# 02_MCU.net
KiCad netlist of a schematic drawn in Altium Designer
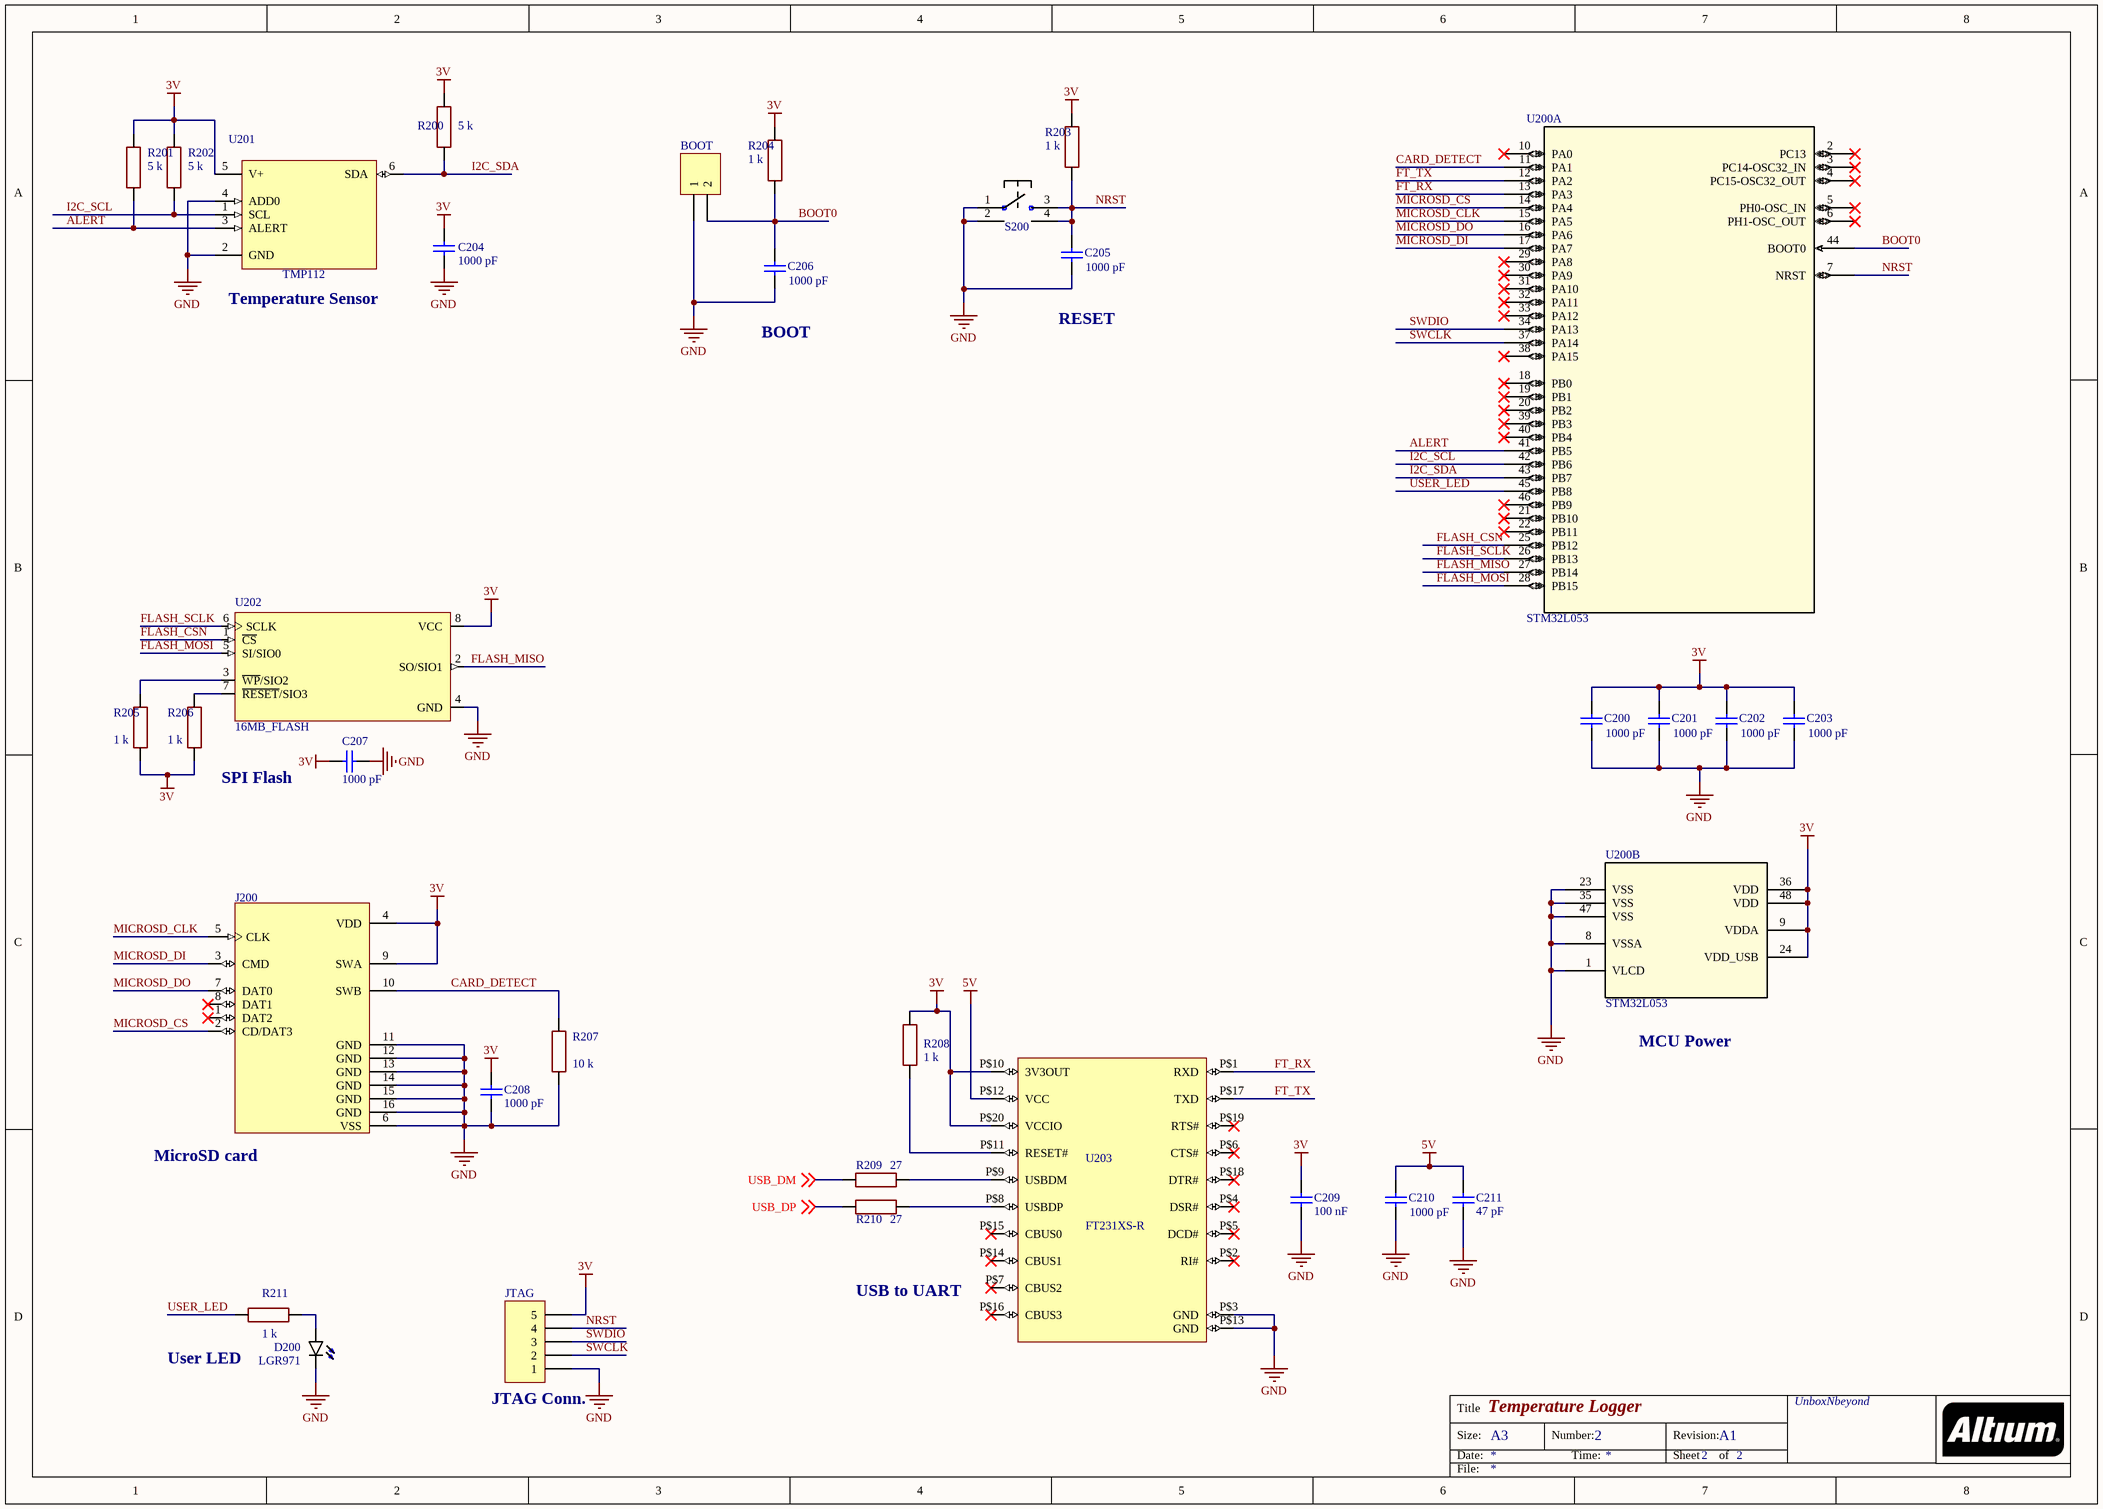
[diagram p0: 02_MCU.SchDoc]

(export (version "E")
  (design (tool "Eeschema 10.0.6"))
  (components
    (comp (ref "BOOT")
      (value "~")
      (footprint "HDR1X2")
      (description "Header, 2-Pin")
      (fields (field (name "PUBLISHER") "Altium Limited"))
      (libsource (lib "Miscellaneous Connectors") (part "Header 2"))
    )
    (comp (ref "C200")
      (value "1000 pF")
      (footprint "C0805")
      (description "CAP CER 1000PF 100V X7R 0805")
      (fields
        (field (name "MANUFACTURER") "KEMET")
        (field (name "MANUFACTURER PART NUMBER") "C0805C102K1RACTU")
      )
      (libsource (lib "temperature_logger_lib") (part "Cap-1000pF"))
    )
    (comp (ref "C201")
      (value "1000 pF")
      (footprint "C0805")
      (description "CAP CER 1000PF 100V X7R 0805")
      (fields
        (field (name "MANUFACTURER") "KEMET")
        (field (name "MANUFACTURER PART NUMBER") "C0805C102K1RACTU")
      )
      (libsource (lib "temperature_logger_lib") (part "Cap-1000pF"))
    )
    (comp (ref "C202")
      (value "1000 pF")
      (footprint "C0805")
      (description "CAP CER 1000PF 100V X7R 0805")
      (fields
        (field (name "MANUFACTURER") "KEMET")
        (field (name "MANUFACTURER PART NUMBER") "C0805C102K1RACTU")
      )
      (libsource (lib "temperature_logger_lib") (part "Cap-1000pF"))
    )
    (comp (ref "C203")
      (value "1000 pF")
      (footprint "C0805")
      (description "CAP CER 1000PF 100V X7R 0805")
      (fields
        (field (name "MANUFACTURER") "KEMET")
        (field (name "MANUFACTURER PART NUMBER") "C0805C102K1RACTU")
      )
      (libsource (lib "temperature_logger_lib") (part "Cap-1000pF"))
    )
    (comp (ref "C204")
      (value "1000 pF")
      (footprint "C0805")
      (description "CAP CER 1000PF 100V X7R 0805")
      (fields
        (field (name "MANUFACTURER") "KEMET")
        (field (name "MANUFACTURER PART NUMBER") "C0805C102K1RACTU")
      )
      (libsource (lib "temperature_logger_lib") (part "Cap-1000pF"))
    )
    (comp (ref "C205")
      (value "1000 pF")
      (footprint "C0805")
      (description "CAP CER 1000PF 100V X7R 0805")
      (fields
        (field (name "MANUFACTURER") "KEMET")
        (field (name "MANUFACTURER PART NUMBER") "C0805C102K1RACTU")
      )
      (libsource (lib "temperature_logger_lib") (part "Cap-1000pF"))
    )
    (comp (ref "C206")
      (value "1000 pF")
      (footprint "C0805")
      (description "CAP CER 1000PF 100V X7R 0805")
      (fields
        (field (name "MANUFACTURER") "KEMET")
        (field (name "MANUFACTURER PART NUMBER") "C0805C102K1RACTU")
      )
      (libsource (lib "temperature_logger_lib") (part "Cap-1000pF"))
    )
    (comp (ref "C207")
      (value "1000 pF")
      (footprint "C0805")
      (description "CAP CER 1000PF 100V X7R 0805")
      (fields
        (field (name "MANUFACTURER") "KEMET")
        (field (name "MANUFACTURER PART NUMBER") "C0805C102K1RACTU")
      )
      (libsource (lib "temperature_logger_lib") (part "Cap-1000pF"))
    )
    (comp (ref "C208")
      (value "1000 pF")
      (footprint "C0805")
      (description "CAP CER 1000PF 100V X7R 0805")
      (fields
        (field (name "MANUFACTURER") "KEMET")
        (field (name "MANUFACTURER PART NUMBER") "C0805C102K1RACTU")
      )
      (libsource (lib "temperature_logger_lib") (part "Cap-1000pF"))
    )
    (comp (ref "C209")
      (value "100 nF")
      (footprint "C0805")
      (description "CAP CER 0.1UF 50V X7R 0805")
      (fields
        (field (name "MANUFACTURER") "KEMET")
        (field (name "MANUFACTURER PART NUMBER") "C0805X104K5RACTU")
      )
      (libsource (lib "temperature_logger_lib") (part "Cap-100nF"))
    )
    (comp (ref "C210")
      (value "1000 pF")
      (footprint "C0805")
      (description "CAP CER 1000PF 100V X7R 0805")
      (fields
        (field (name "MANUFACTURER") "KEMET")
        (field (name "MANUFACTURER PART NUMBER") "C0805C102K1RACTU")
      )
      (libsource (lib "temperature_logger_lib") (part "Cap-1000pF"))
    )
    (comp (ref "C211")
      (value "47 pF")
      (footprint "C0805")
      (description "CAP CER 47PF 1KV C0G/NP0 0805")
      (fields
        (field (name "MANUFACTURER") "KEMET")
        (field (name "MANUFACTURER PART NUMBER") "C0805C470JDGACTU")
      )
      (libsource (lib "temperature_logger_lib") (part "Cap-47pF"))
    )
    (comp (ref "D200")
      (value "LGR971")
      (footprint "D0805")
      (description "LED GREEN DIFFUSED 0805 SMD")
      (fields
        (field (name "MANUFACTURER") "Osram Opto")
        (field (name "MANUFACTURER PART NUMBER") "LG R971-KN-1")
      )
      (libsource (lib "temperature_logger_lib") (part "LGR971"))
    )
    (comp (ref "J200")
      (value "MicroSD")
      (footprint "MicroSD")
      (description "MICRO SD PUSH PUSH LOW PROFILE TYPE")
      (fields
        (field (name "MANUFACTURER PART NUMBER") "2201778-1")
        (field (name "MANUFACTURER") "TE Connectivity")
      )
      (libsource (lib "temperature_logger_lib") (part "MicroSD"))
    )
    (comp (ref "JTAG")
      (value "~")
      (footprint "HDR1X5")
      (description "Header, 5-Pin")
      (fields (field (name "PUBLISHER") "Altium Limited"))
      (libsource (lib "Miscellaneous Connectors") (part "Header 5"))
    )
    (comp (ref "R200")
      (value "5 k")
      (footprint "R0805")
      (description "RES SMD 4.7K OHM 0.1% 1/8W 0805")
      (fields
        (field (name "MANUFACTURER") "Panasonic Electronic Components")
        (field (name "MANUFACTURER PART NUMBER") "ERA-6AEB472V")
      )
      (libsource (lib "temperature_logger_lib") (part "Res-5k"))
    )
    (comp (ref "R201")
      (value "5 k")
      (footprint "R0805")
      (description "RES SMD 4.7K OHM 0.1% 1/8W 0805")
      (fields
        (field (name "MANUFACTURER") "Panasonic Electronic Components")
        (field (name "MANUFACTURER PART NUMBER") "ERA-6AEB472V")
      )
      (libsource (lib "temperature_logger_lib") (part "Res-5k"))
    )
    (comp (ref "R202")
      (value "5 k")
      (footprint "R0805")
      (description "RES SMD 4.7K OHM 0.1% 1/8W 0805")
      (fields
        (field (name "MANUFACTURER") "Panasonic Electronic Components")
        (field (name "MANUFACTURER PART NUMBER") "ERA-6AEB472V")
      )
      (libsource (lib "temperature_logger_lib") (part "Res-5k"))
    )
    (comp (ref "R203")
      (value "1 k")
      (footprint "R0805")
      (description "RES 1K OHM 0.1% 1/5W 0805")
      (fields
        (field (name "MANUFACTURER") "Vishay Dale")
        (field (name "MANUFACTURER PART NUMBER") "TNPW08051K00BEEA")
      )
      (libsource (lib "temperature_logger_lib") (part "Res-1k"))
    )
    (comp (ref "R204")
      (value "1 k")
      (footprint "R0805")
      (description "RES 1K OHM 0.1% 1/5W 0805")
      (fields
        (field (name "MANUFACTURER") "Vishay Dale")
        (field (name "MANUFACTURER PART NUMBER") "TNPW08051K00BEEA")
      )
      (libsource (lib "temperature_logger_lib") (part "Res-1k"))
    )
    (comp (ref "R205")
      (value "1 k")
      (footprint "R0805")
      (description "RES 1K OHM 0.1% 1/5W 0805")
      (fields
        (field (name "MANUFACTURER") "Vishay Dale")
        (field (name "MANUFACTURER PART NUMBER") "TNPW08051K00BEEA")
      )
      (libsource (lib "") (part "Res-1k_1"))
    )
    (comp (ref "R206")
      (value "1 k")
      (footprint "R0805")
      (description "RES 1K OHM 0.1% 1/5W 0805")
      (fields
        (field (name "MANUFACTURER") "Vishay Dale")
        (field (name "MANUFACTURER PART NUMBER") "TNPW08051K00BEEA")
      )
      (libsource (lib "") (part "Res-1k_1"))
    )
    (comp (ref "R207")
      (value "10 k")
      (footprint "R0805")
      (description "RES SMD 10K OHM 0.1% 1/8W 0805")
      (fields
        (field (name "MANUFACTURER") "Panasonic Electronic Components")
        (field (name "MANUFACTURER PART NUMBER") "ERA-6AEB103V")
      )
      (libsource (lib "temperature_logger_lib") (part "Res-10k"))
    )
    (comp (ref "R208")
      (value "1 k")
      (footprint "R0805")
      (description "RES 1K OHM 0.1% 1/5W 0805")
      (fields
        (field (name "MANUFACTURER") "Vishay Dale")
        (field (name "MANUFACTURER PART NUMBER") "TNPW08051K00BEEA")
      )
      (libsource (lib "temperature_logger_lib") (part "Res-1k"))
    )
    (comp (ref "R209")
      (value "27")
      (footprint "R0805")
      (description "RES SMD 27 OHM 5% 1/8W 0805")
      (fields
        (field (name "MANUFACTURER") "Panasonic Electronic Components")
        (field (name "MANUFACTURER PART NUMBER") "ERJ-6GEYJ270V")
      )
      (libsource (lib "temperature_logger_lib") (part "Res-27"))
    )
    (comp (ref "R210")
      (value "27")
      (footprint "R0805")
      (description "RES SMD 27 OHM 5% 1/8W 0805")
      (fields
        (field (name "MANUFACTURER") "Panasonic Electronic Components")
        (field (name "MANUFACTURER PART NUMBER") "ERJ-6GEYJ270V")
      )
      (libsource (lib "temperature_logger_lib") (part "Res-27"))
    )
    (comp (ref "R211")
      (value "1 k")
      (footprint "R0805")
      (description "RES 1K OHM 0.1% 1/5W 0805")
      (fields
        (field (name "MANUFACTURER") "Vishay Dale")
        (field (name "MANUFACTURER PART NUMBER") "TNPW08051K00BEEA")
      )
      (libsource (lib "") (part "Res-1k_2"))
    )
    (comp (ref "S200")
      (value "Switch_tactile")
      (footprint "Tactile1")
      (description "SWITCH TACTILE SPST-NO 0.05A 12V")
      (fields
        (field (name "MANUFACTURER") "C&K Components")
        (field (name "MANUFACTURER PART NUMBER") "PTS645SM43SMTR")
      )
      (libsource (lib "temperature_logger_lib") (part "Switch_tactile"))
    )
    (comp (ref "U200")
      (value "STM32L053")
      (footprint "LQFP48-7x7mm")
      (description "IC MCU 32BIT 64KB FLASH 48LQFP")
      (fields
        (field (name "MANUFACTURER PART NUMBER") "STM32L053C8T6")
        (field (name "MANUFACTURER") "STMicroelectronics")
      )
      (libsource (lib "temperature_logger_lib") (part "STM32L0x3CL4"))
    )
    (comp (ref "U201")
      (value "TMP112")
      (footprint "SOT563")
      (fields
        (field (name "MANUFACTURER PART NUMBER") "TMP112AIDRLT")
        (field (name "MANUFACTURER") "Texas Instruments")
      )
      (libsource (lib "temperature_logger_lib") (part "TMP112AIDRLT"))
    )
    (comp (ref "U202")
      (value "16MB_FLASH")
      (footprint "8-SOIC")
      (description "IC FLASH 16M SPI 80MHZ 8SOP")
      (fields
        (field (name "MANUFACTURER PART NUMBER") "MX25R1635FM2IL0")
        (field (name "MANUFACTURER") "Macronix")
      )
      (libsource (lib "temperature_logger_lib") (part "MX25R1635"))
    )
    (comp (ref "U203")
      (value "FT231XS-R")
      (footprint "SSOP20")
      (description "USB Full Speed to Full Handshake UART with USB Charger Detection")
      (fields (field (name "MANUFACTURER") "FTDI"))
      (libsource (lib "temperature_logger_lib") (part "FT231XS-R"))
    )
  )
  (nets
    (net (code "1") (name "/ALERT") (class "Default")
      (node (ref "R201") (pin "2") (pinfunction "2_2") (pintype "passive"))
      (node (ref "U200") (pin "41") (pinfunction "PB5_41") (pintype "bidirectional"))
      (node (ref "U201") (pin "3") (pinfunction "ALERT_3") (pintype "input"))
    )
    (net (code "2") (name "/BOOT0") (class "Default")
      (node (ref "BOOT") (pin "2") (pinfunction "2_2") (pintype "passive"))
      (node (ref "C206") (pin "2") (pinfunction "2_2") (pintype "passive"))
      (node (ref "R204") (pin "2") (pinfunction "2_2") (pintype "passive"))
      (node (ref "U200") (pin "44") (pinfunction "BOOT0_44") (pintype "input"))
    )
    (net (code "3") (name "/CARD_DETECT") (class "Default")
      (node (ref "J200") (pin "10") (pinfunction "SWB_10") (pintype "passive"))
      (node (ref "R207") (pin "1") (pinfunction "1_1") (pintype "passive"))
      (node (ref "U200") (pin "11") (pinfunction "PA1_11") (pintype "bidirectional"))
    )
    (net (code "4") (name "/FLASH_CSN") (class "Default")
      (node (ref "U200") (pin "25") (pinfunction "PB12_25") (pintype "bidirectional"))
      (node (ref "U202") (pin "1") (pinfunction "~{CS}_1") (pintype "input"))
    )
    (net (code "5") (name "/FLASH_MISO") (class "Default")
      (node (ref "U200") (pin "27") (pinfunction "PB14_27") (pintype "bidirectional"))
      (node (ref "U202") (pin "2") (pinfunction "SO/SIO1_2") (pintype "output"))
    )
    (net (code "6") (name "/FLASH_MOSI") (class "Default")
      (node (ref "U200") (pin "28") (pinfunction "PB15_28") (pintype "bidirectional"))
      (node (ref "U202") (pin "5") (pinfunction "SI/SIO0_5") (pintype "input"))
    )
    (net (code "7") (name "/FLASH_SCLK") (class "Default")
      (node (ref "U200") (pin "26") (pinfunction "PB13_26") (pintype "bidirectional"))
      (node (ref "U202") (pin "6") (pinfunction "SCLK_6") (pintype "input"))
    )
    (net (code "8") (name "/FT_RX") (class "Default")
      (node (ref "U200") (pin "13") (pinfunction "PA3_13") (pintype "bidirectional"))
      (node (ref "U203") (pin "P$1") (pinfunction "RXD_P$1") (pintype "bidirectional"))
    )
    (net (code "9") (name "/FT_TX") (class "Default")
      (node (ref "U200") (pin "12") (pinfunction "PA2_12") (pintype "bidirectional"))
      (node (ref "U203") (pin "P$17") (pinfunction "TXD_P$17") (pintype "bidirectional"))
    )
    (net (code "10") (name "/I2C_SCL") (class "Default")
      (node (ref "R202") (pin "2") (pinfunction "2_2") (pintype "passive"))
      (node (ref "U200") (pin "42") (pinfunction "PB6_42") (pintype "bidirectional"))
      (node (ref "U201") (pin "1") (pinfunction "SCL_1") (pintype "input"))
    )
    (net (code "11") (name "/I2C_SDA") (class "Default")
      (node (ref "R200") (pin "2") (pinfunction "2_2") (pintype "passive"))
      (node (ref "U200") (pin "43") (pinfunction "PB7_43") (pintype "bidirectional"))
      (node (ref "U201") (pin "6") (pinfunction "SDA_6") (pintype "bidirectional"))
    )
    (net (code "12") (name "/MICROSD_CLK") (class "Default")
      (node (ref "J200") (pin "5") (pinfunction "CLK_5") (pintype "input"))
      (node (ref "U200") (pin "15") (pinfunction "PA5_15") (pintype "bidirectional"))
    )
    (net (code "13") (name "/MICROSD_CS") (class "Default")
      (node (ref "J200") (pin "2") (pinfunction "CD/DAT3_2") (pintype "bidirectional"))
      (node (ref "U200") (pin "14") (pinfunction "PA4_14") (pintype "bidirectional"))
    )
    (net (code "14") (name "/MICROSD_DI") (class "Default")
      (node (ref "J200") (pin "3") (pinfunction "CMD_3") (pintype "bidirectional"))
      (node (ref "U200") (pin "17") (pinfunction "PA7_17") (pintype "bidirectional"))
    )
    (net (code "15") (name "/MICROSD_DO") (class "Default")
      (node (ref "J200") (pin "7") (pinfunction "DAT0_7") (pintype "bidirectional"))
      (node (ref "U200") (pin "16") (pinfunction "PA6_16") (pintype "bidirectional"))
    )
    (net (code "16") (name "/NRST") (class "Default")
      (node (ref "C205") (pin "2") (pinfunction "2_2") (pintype "passive"))
      (node (ref "JTAG") (pin "4") (pinfunction "4_4") (pintype "passive"))
      (node (ref "R203") (pin "2") (pinfunction "2_2") (pintype "passive"))
      (node (ref "S200") (pin "3") (pinfunction "P$2_3") (pintype "passive"))
      (node (ref "S200") (pin "4") (pinfunction "P$2_4") (pintype "passive"))
      (node (ref "U200") (pin "7") (pinfunction "NRST_7") (pintype "bidirectional"))
    )
    (net (code "17") (name "/SWCLK") (class "Default")
      (node (ref "JTAG") (pin "2") (pinfunction "2_2") (pintype "passive"))
      (node (ref "U200") (pin "37") (pinfunction "PA14_37") (pintype "bidirectional"))
    )
    (net (code "18") (name "/SWDIO") (class "Default")
      (node (ref "JTAG") (pin "3") (pinfunction "3_3") (pintype "passive"))
      (node (ref "U200") (pin "34") (pinfunction "PA13_34") (pintype "bidirectional"))
    )
    (net (code "19") (name "/USER_LED") (class "Default")
      (node (ref "R211") (pin "2") (pinfunction "2_2") (pintype "passive"))
      (node (ref "U200") (pin "45") (pinfunction "PB8_45") (pintype "bidirectional"))
    )
    (net (code "20") (name "3V") (class "Default")
      (node (ref "C200") (pin "2") (pinfunction "2_2") (pintype "passive"))
      (node (ref "C201") (pin "2") (pinfunction "2_2") (pintype "passive"))
      (node (ref "C202") (pin "2") (pinfunction "2_2") (pintype "passive"))
      (node (ref "C203") (pin "2") (pinfunction "2_2") (pintype "passive"))
      (node (ref "C204") (pin "2") (pinfunction "2_2") (pintype "passive"))
      (node (ref "C207") (pin "2") (pinfunction "2_2") (pintype "passive"))
      (node (ref "C208") (pin "1") (pinfunction "1_1") (pintype "passive"))
      (node (ref "C209") (pin "2") (pinfunction "2_2") (pintype "passive"))
      (node (ref "J200") (pin "4") (pinfunction "VDD_4") (pintype "power_in"))
      (node (ref "J200") (pin "9") (pinfunction "SWA_9") (pintype "passive"))
      (node (ref "JTAG") (pin "5") (pinfunction "5_5") (pintype "passive"))
      (node (ref "R200") (pin "1") (pinfunction "1_1") (pintype "passive"))
      (node (ref "R201") (pin "1") (pinfunction "1_1") (pintype "passive"))
      (node (ref "R202") (pin "1") (pinfunction "1_1") (pintype "passive"))
      (node (ref "R203") (pin "1") (pinfunction "1_1") (pintype "passive"))
      (node (ref "R204") (pin "1") (pinfunction "1_1") (pintype "passive"))
      (node (ref "R205") (pin "1") (pinfunction "1_1") (pintype "passive"))
      (node (ref "R206") (pin "1") (pinfunction "1_1") (pintype "passive"))
      (node (ref "R208") (pin "1") (pinfunction "1_1") (pintype "passive"))
      (node (ref "U200") (pin "24") (pinfunction "VDD_USB_24") (pintype "power_in"))
      (node (ref "U200") (pin "36") (pinfunction "VDD_36") (pintype "power_in"))
      (node (ref "U200") (pin "48") (pinfunction "VDD_48") (pintype "power_in"))
      (node (ref "U200") (pin "9") (pinfunction "VDDA_9") (pintype "power_in"))
      (node (ref "U201") (pin "5") (pinfunction "V+_5") (pintype "power_in"))
      (node (ref "U202") (pin "8") (pinfunction "VCC_8") (pintype "power_in"))
      (node (ref "U203") (pin "P$10") (pinfunction "3V3OUT_P$10") (pintype "bidirectional"))
      (node (ref "U203") (pin "P$20") (pinfunction "VCCIO_P$20") (pintype "bidirectional"))
    )
    (net (code "21") (name "5V") (class "Default")
      (node (ref "C210") (pin "2") (pinfunction "2_2") (pintype "passive"))
      (node (ref "C211") (pin "2") (pinfunction "2_2") (pintype "passive"))
      (node (ref "U203") (pin "P$12") (pinfunction "VCC_P$12") (pintype "bidirectional"))
    )
    (net (code "22") (name "GND") (class "Default")
      (node (ref "BOOT") (pin "1") (pinfunction "1_1") (pintype "passive"))
      (node (ref "C200") (pin "1") (pinfunction "1_1") (pintype "passive"))
      (node (ref "C201") (pin "1") (pinfunction "1_1") (pintype "passive"))
      (node (ref "C202") (pin "1") (pinfunction "1_1") (pintype "passive"))
      (node (ref "C203") (pin "1") (pinfunction "1_1") (pintype "passive"))
      (node (ref "C204") (pin "1") (pinfunction "1_1") (pintype "passive"))
      (node (ref "C205") (pin "1") (pinfunction "1_1") (pintype "passive"))
      (node (ref "C206") (pin "1") (pinfunction "1_1") (pintype "passive"))
      (node (ref "C207") (pin "1") (pinfunction "1_1") (pintype "passive"))
      (node (ref "C208") (pin "2") (pinfunction "2_2") (pintype "passive"))
      (node (ref "C209") (pin "1") (pinfunction "1_1") (pintype "passive"))
      (node (ref "C210") (pin "1") (pinfunction "1_1") (pintype "passive"))
      (node (ref "C211") (pin "1") (pinfunction "1_1") (pintype "passive"))
      (node (ref "D200") (pin "C") (pinfunction "C_C") (pintype "passive"))
      (node (ref "J200") (pin "11") (pinfunction "GND_11") (pintype "power_in"))
      (node (ref "J200") (pin "12") (pinfunction "GND_12") (pintype "power_in"))
      (node (ref "J200") (pin "13") (pinfunction "GND_13") (pintype "power_in"))
      (node (ref "J200") (pin "14") (pinfunction "GND_14") (pintype "power_in"))
      (node (ref "J200") (pin "15") (pinfunction "GND_15") (pintype "power_in"))
      (node (ref "J200") (pin "16") (pinfunction "GND_16") (pintype "power_in"))
      (node (ref "J200") (pin "6") (pinfunction "VSS_6") (pintype "power_in"))
      (node (ref "JTAG") (pin "1") (pinfunction "1_1") (pintype "passive"))
      (node (ref "R207") (pin "2") (pinfunction "2_2") (pintype "passive"))
      (node (ref "S200") (pin "1") (pinfunction "P$1_1") (pintype "passive"))
      (node (ref "S200") (pin "2") (pinfunction "P$1_2") (pintype "passive"))
      (node (ref "U200") (pin "1") (pinfunction "VLCD_1") (pintype "power_in"))
      (node (ref "U200") (pin "23") (pinfunction "VSS_23") (pintype "power_in"))
      (node (ref "U200") (pin "35") (pinfunction "VSS_35") (pintype "power_in"))
      (node (ref "U200") (pin "47") (pinfunction "VSS_47") (pintype "power_in"))
      (node (ref "U200") (pin "8") (pinfunction "VSSA_8") (pintype "power_in"))
      (node (ref "U201") (pin "2") (pinfunction "GND_2") (pintype "passive"))
      (node (ref "U201") (pin "4") (pinfunction "ADD0_4") (pintype "input"))
      (node (ref "U202") (pin "4") (pinfunction "GND_4") (pintype "power_in"))
      (node (ref "U203") (pin "P$13") (pinfunction "GND_P$13") (pintype "bidirectional"))
      (node (ref "U203") (pin "P$3") (pinfunction "GND_P$3") (pintype "bidirectional"))
    )
    (net (code "23") (name "Net-(D200-PadA)") (class "Default")
      (node (ref "D200") (pin "A") (pinfunction "A_A") (pintype "passive"))
      (node (ref "R211") (pin "1") (pinfunction "1_1") (pintype "passive"))
    )
    (net (code "24") (name "Net-(U202-~{RESET}{slash}SIO3)") (class "Default")
      (node (ref "R206") (pin "2") (pinfunction "2_2") (pintype "passive"))
      (node (ref "U202") (pin "7") (pinfunction "~{RESET}/SIO3_7") (pintype "bidirectional"))
    )
    (net (code "25") (name "Net-(U202-~{WP}{slash}SIO2)") (class "Default")
      (node (ref "R205") (pin "2") (pinfunction "2_2") (pintype "passive"))
      (node (ref "U202") (pin "3") (pinfunction "~{WP}/SIO2_3") (pintype "bidirectional"))
    )
    (net (code "26") (name "Net-(U203-RESET#)") (class "Default")
      (node (ref "R208") (pin "2") (pinfunction "2_2") (pintype "passive"))
      (node (ref "U203") (pin "P$11") (pinfunction "RESET#_P$11") (pintype "bidirectional"))
    )
    (net (code "27") (name "Net-(U203-USBDM)") (class "Default")
      (node (ref "R209") (pin "1") (pinfunction "1_1") (pintype "passive"))
      (node (ref "U203") (pin "P$9") (pinfunction "USBDM_P$9") (pintype "bidirectional"))
    )
    (net (code "28") (name "Net-(U203-USBDP)") (class "Default")
      (node (ref "R210") (pin "1") (pinfunction "1_1") (pintype "passive"))
      (node (ref "U203") (pin "P$8") (pinfunction "USBDP_P$8") (pintype "bidirectional"))
    )
    (net (code "29") (name "USB_DM") (class "Default")
      (node (ref "R209") (pin "2") (pinfunction "2_2") (pintype "passive"))
    )
    (net (code "30") (name "USB_DP") (class "Default")
      (node (ref "R210") (pin "2") (pinfunction "2_2") (pintype "passive"))
    )
    (net (code "31") (name "unconnected-(J200-DAT1-Pad8)") (class "Default")
      (node (ref "J200") (pin "8") (pinfunction "DAT1_8") (pintype "bidirectional+no_connect"))
    )
    (net (code "32") (name "unconnected-(J200-DAT2-Pad1)") (class "Default")
      (node (ref "J200") (pin "1") (pinfunction "DAT2_1") (pintype "bidirectional+no_connect"))
    )
    (net (code "33") (name "unconnected-(U200A-PA0-Pad10)") (class "Default")
      (node (ref "U200") (pin "10") (pinfunction "PA0_10") (pintype "bidirectional+no_connect"))
    )
    (net (code "34") (name "unconnected-(U200A-PA8-Pad29)") (class "Default")
      (node (ref "U200") (pin "29") (pinfunction "PA8_29") (pintype "bidirectional+no_connect"))
    )
    (net (code "35") (name "unconnected-(U200A-PA9-Pad30)") (class "Default")
      (node (ref "U200") (pin "30") (pinfunction "PA9_30") (pintype "bidirectional+no_connect"))
    )
    (net (code "36") (name "unconnected-(U200A-PA10-Pad31)") (class "Default")
      (node (ref "U200") (pin "31") (pinfunction "PA10_31") (pintype "bidirectional+no_connect"))
    )
    (net (code "37") (name "unconnected-(U200A-PA11-Pad32)") (class "Default")
      (node (ref "U200") (pin "32") (pinfunction "PA11_32") (pintype "bidirectional+no_connect"))
    )
    (net (code "38") (name "unconnected-(U200A-PA12-Pad33)") (class "Default")
      (node (ref "U200") (pin "33") (pinfunction "PA12_33") (pintype "bidirectional+no_connect"))
    )
    (net (code "39") (name "unconnected-(U200A-PA15-Pad38)") (class "Default")
      (node (ref "U200") (pin "38") (pinfunction "PA15_38") (pintype "bidirectional+no_connect"))
    )
    (net (code "40") (name "unconnected-(U200A-PB0-Pad18)") (class "Default")
      (node (ref "U200") (pin "18") (pinfunction "PB0_18") (pintype "bidirectional+no_connect"))
    )
    (net (code "41") (name "unconnected-(U200A-PB1-Pad19)") (class "Default")
      (node (ref "U200") (pin "19") (pinfunction "PB1_19") (pintype "bidirectional+no_connect"))
    )
    (net (code "42") (name "unconnected-(U200A-PB2-Pad20)") (class "Default")
      (node (ref "U200") (pin "20") (pinfunction "PB2_20") (pintype "bidirectional+no_connect"))
    )
    (net (code "43") (name "unconnected-(U200A-PB3-Pad39)") (class "Default")
      (node (ref "U200") (pin "39") (pinfunction "PB3_39") (pintype "bidirectional+no_connect"))
    )
    (net (code "44") (name "unconnected-(U200A-PB4-Pad40)") (class "Default")
      (node (ref "U200") (pin "40") (pinfunction "PB4_40") (pintype "bidirectional+no_connect"))
    )
    (net (code "45") (name "unconnected-(U200A-PB9-Pad46)") (class "Default")
      (node (ref "U200") (pin "46") (pinfunction "PB9_46") (pintype "bidirectional+no_connect"))
    )
    (net (code "46") (name "unconnected-(U200A-PB10-Pad21)") (class "Default")
      (node (ref "U200") (pin "21") (pinfunction "PB10_21") (pintype "bidirectional+no_connect"))
    )
    (net (code "47") (name "unconnected-(U200A-PB11-Pad22)") (class "Default")
      (node (ref "U200") (pin "22") (pinfunction "PB11_22") (pintype "bidirectional+no_connect"))
    )
    (net (code "48") (name "unconnected-(U200A-PC13-Pad2)") (class "Default")
      (node (ref "U200") (pin "2") (pinfunction "PC13_2") (pintype "bidirectional+no_connect"))
    )
    (net (code "49") (name "unconnected-(U200A-PC14-OSC32_IN-Pad3)") (class "Default")
      (node (ref "U200") (pin "3") (pinfunction "PC14-OSC32_IN_3") (pintype "bidirectional+no_connect"))
    )
    (net (code "50") (name "unconnected-(U200A-PC15-OSC32_OUT-Pad4)") (class "Default")
      (node (ref "U200") (pin "4") (pinfunction "PC15-OSC32_OUT_4") (pintype "bidirectional+no_connect"))
    )
    (net (code "51") (name "unconnected-(U200A-PH0-OSC_IN-Pad5)") (class "Default")
      (node (ref "U200") (pin "5") (pinfunction "PH0-OSC_IN_5") (pintype "bidirectional+no_connect"))
    )
    (net (code "52") (name "unconnected-(U200A-PH1-OSC_OUT-Pad6)") (class "Default")
      (node (ref "U200") (pin "6") (pinfunction "PH1-OSC_OUT_6") (pintype "bidirectional+no_connect"))
    )
    (net (code "53") (name "unconnected-(U203-CBUS0-PadP$15)") (class "Default")
      (node (ref "U203") (pin "P$15") (pinfunction "CBUS0_P$15") (pintype "bidirectional+no_connect"))
    )
    (net (code "54") (name "unconnected-(U203-CBUS1-PadP$14)") (class "Default")
      (node (ref "U203") (pin "P$14") (pinfunction "CBUS1_P$14") (pintype "bidirectional+no_connect"))
    )
    (net (code "55") (name "unconnected-(U203-CBUS2-PadP$7)") (class "Default")
      (node (ref "U203") (pin "P$7") (pinfunction "CBUS2_P$7") (pintype "bidirectional+no_connect"))
    )
    (net (code "56") (name "unconnected-(U203-CBUS3-PadP$16)") (class "Default")
      (node (ref "U203") (pin "P$16") (pinfunction "CBUS3_P$16") (pintype "bidirectional+no_connect"))
    )
    (net (code "57") (name "unconnected-(U203-CTS#-PadP$6)") (class "Default")
      (node (ref "U203") (pin "P$6") (pinfunction "CTS#_P$6") (pintype "bidirectional+no_connect"))
    )
    (net (code "58") (name "unconnected-(U203-DCD#-PadP$5)") (class "Default")
      (node (ref "U203") (pin "P$5") (pinfunction "DCD#_P$5") (pintype "bidirectional+no_connect"))
    )
    (net (code "59") (name "unconnected-(U203-DSR#-PadP$4)") (class "Default")
      (node (ref "U203") (pin "P$4") (pinfunction "DSR#_P$4") (pintype "bidirectional+no_connect"))
    )
    (net (code "60") (name "unconnected-(U203-DTR#-PadP$18)") (class "Default")
      (node (ref "U203") (pin "P$18") (pinfunction "DTR#_P$18") (pintype "bidirectional+no_connect"))
    )
    (net (code "61") (name "unconnected-(U203-RI#-PadP$2)") (class "Default")
      (node (ref "U203") (pin "P$2") (pinfunction "RI#_P$2") (pintype "bidirectional+no_connect"))
    )
    (net (code "62") (name "unconnected-(U203-RTS#-PadP$19)") (class "Default")
      (node (ref "U203") (pin "P$19") (pinfunction "RTS#_P$19") (pintype "bidirectional+no_connect"))
    )
  )
)
